# Sensor_Module_0x01_Template_v1.net
KiCad netlist of a schematic drawn in EAGLE
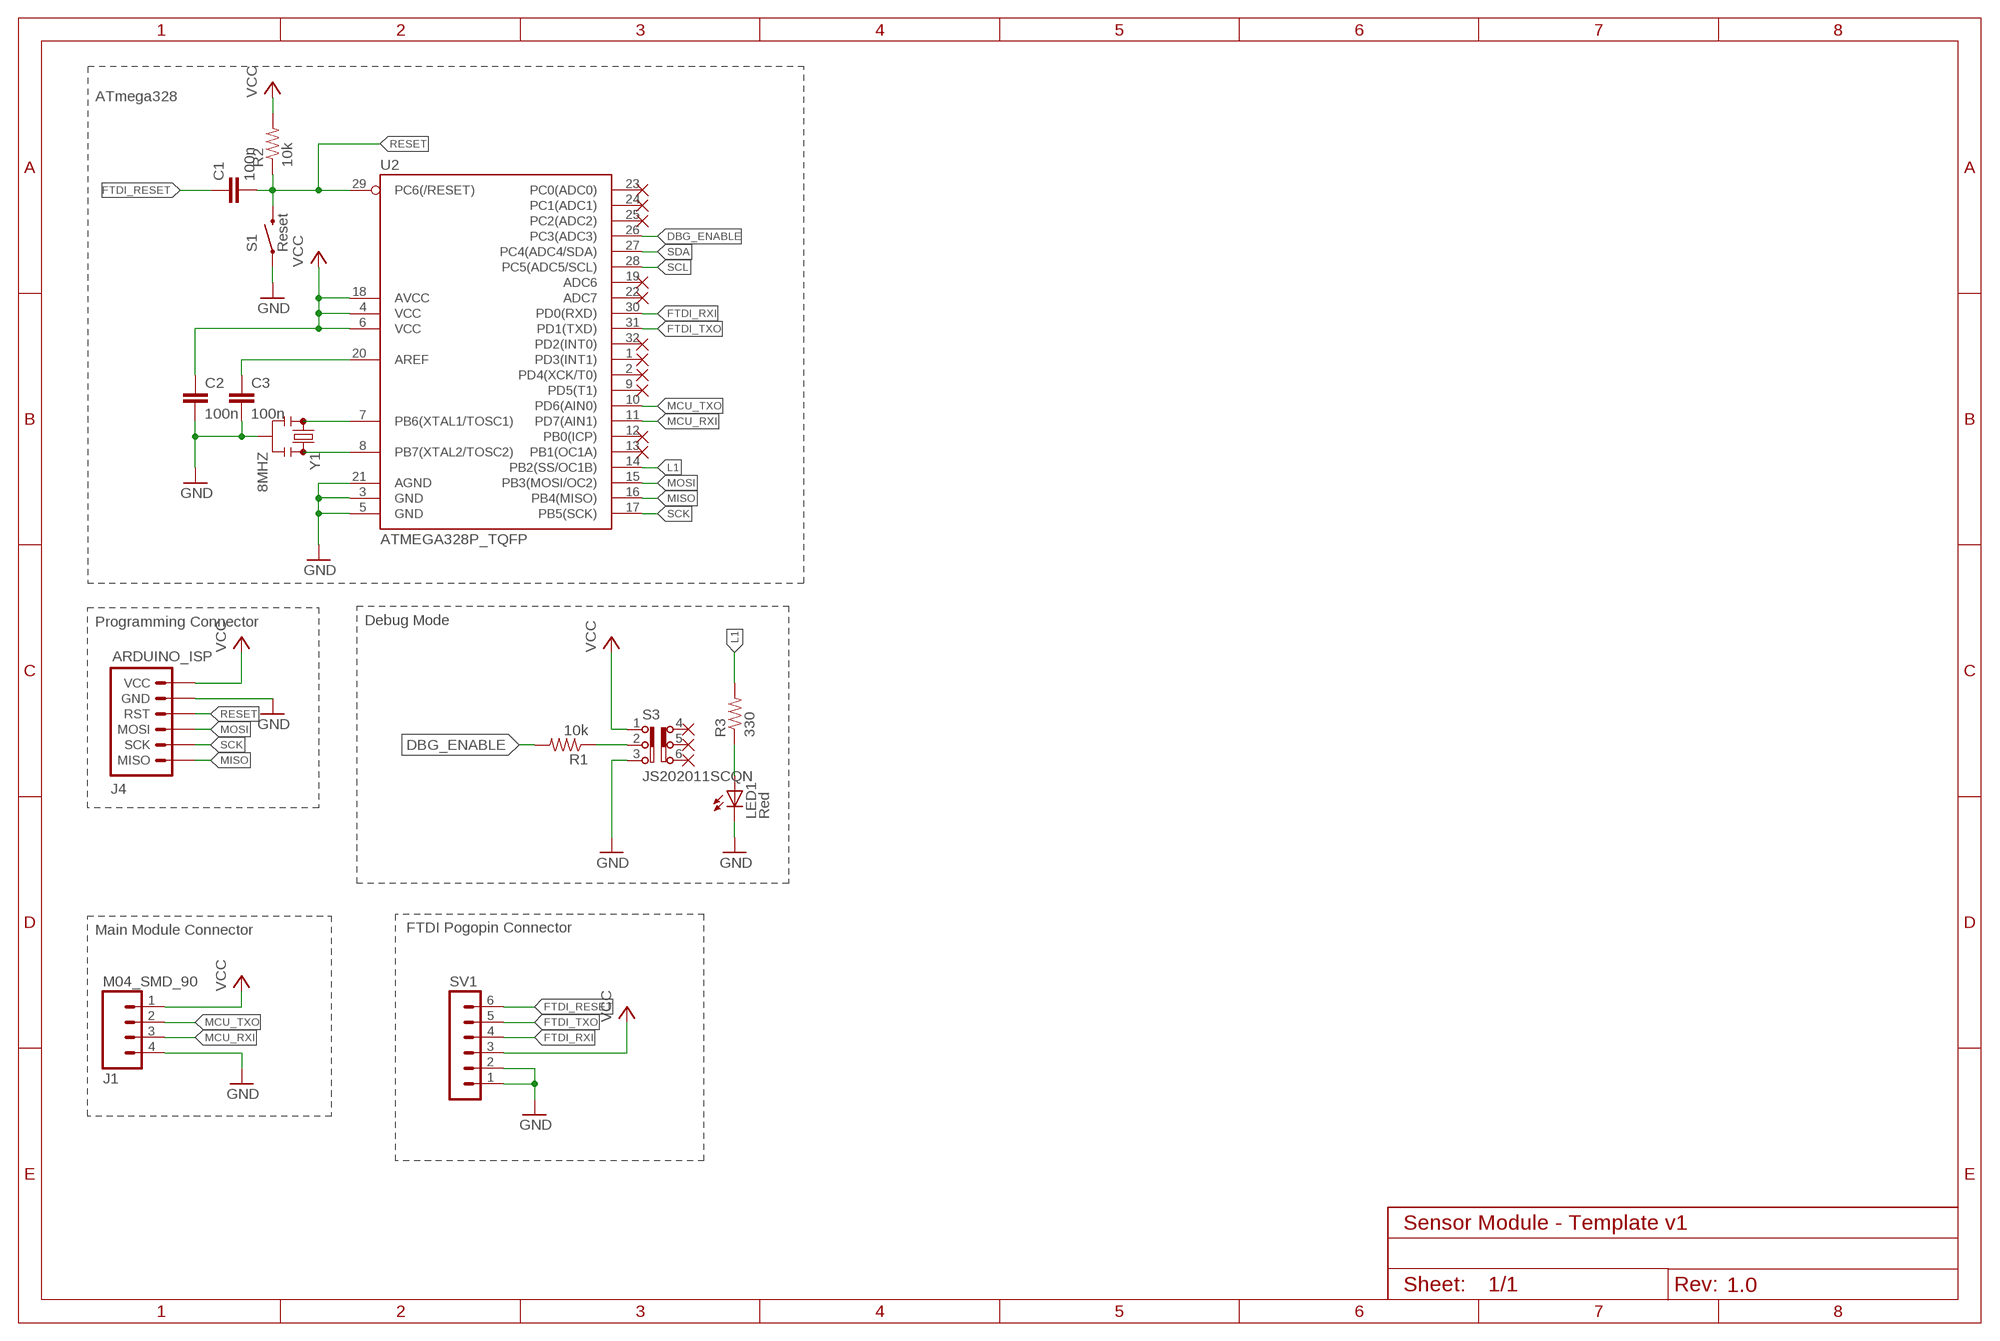
[diagram p0: schematic, sheet 1]

(export (version "E")
  (design (tool "Eeschema 10.0.6"))
  (components
    (comp (ref "C1")
      (value "100n")
      (footprint "eagle-import:C0805")
      (libsource (lib "eagle-import") (part "C"))
    )
    (comp (ref "C2")
      (value "100n")
      (footprint "eagle-import:C0805")
      (libsource (lib "eagle-import") (part "C"))
    )
    (comp (ref "C3")
      (value "100n")
      (footprint "eagle-import:C0805")
      (libsource (lib "eagle-import") (part "C"))
    )
    (comp (ref "J1")
      (value "M04_SMD_90")
      (footprint "eagle-import:M04_SMD_90")
      (libsource (lib "eagle-import") (part "M04_SMD_90"))
    )
    (comp (ref "J4")
      (value "ARDUINO_ISP")
      (footprint "eagle-import:M-2X3")
      (libsource (lib "eagle-import") (part "ARDUINO_ISP"))
    )
    (comp (ref "LED1")
      (value "Red")
      (footprint "eagle-import:SML0805")
      (libsource (lib "eagle-import") (part "LEDSML0805"))
    )
    (comp (ref "R1")
      (value "10k")
      (footprint "eagle-import:0805")
      (libsource (lib "eagle-import") (part "RESISTOR0805-RES"))
    )
    (comp (ref "R2")
      (value "10k")
      (footprint "eagle-import:0805")
      (libsource (lib "eagle-import") (part "RESISTOR0805-RES"))
    )
    (comp (ref "R3")
      (value "330")
      (footprint "eagle-import:0805")
      (libsource (lib "eagle-import") (part "RESISTOR0805-RES"))
    )
    (comp (ref "S1")
      (value "Reset")
      (footprint "eagle-import:M-PUSHBUTTON-SMD")
      (libsource (lib "eagle-import") (part "PUSHBUTTON"))
    )
    (comp (ref "S3")
      (value "JS202011SCQN")
      (footprint "eagle-import:JS202011SCQN")
      (libsource (lib "eagle-import") (part "JS202011SCQN"))
    )
    (comp (ref "SV1")
      (value "MA06-1")
      (footprint "eagle-import:MA06-1")
      (libsource (lib "eagle-import") (part "MA06-1"))
    )
    (comp (ref "U2")
      (value "ATMEGA328P_TQFP")
      (footprint "eagle-import:TQFP32-08")
      (libsource (lib "eagle-import") (part "ATMEGA328P_TQFP"))
    )
    (comp (ref "Y1")
      (value "8MHZ")
      (footprint "eagle-import:RESONATOR-SMD")
      (libsource (lib "eagle-import") (part "RESONATOR8MHZ"))
    )
  )
  (nets
    (net (code "1") (name "DBG_ENABLE") (class "Default")
      (node (ref "R1") (pin "2") (pinfunction "2_2") (pintype "passive"))
      (node (ref "U2") (pin "26") (pinfunction "PC3(ADC3)_26") (pintype "bidirectional"))
    )
    (net (code "2") (name "FTDI_RESET") (class "Default")
      (node (ref "C1") (pin "1") (pinfunction "1_1") (pintype "passive"))
      (node (ref "SV1") (pin "6") (pinfunction "6_6") (pintype "passive"))
    )
    (net (code "3") (name "FTDI_RXI") (class "Default")
      (node (ref "SV1") (pin "4") (pinfunction "4_4") (pintype "passive"))
      (node (ref "U2") (pin "30") (pinfunction "PD0(RXD)_30") (pintype "bidirectional"))
    )
    (net (code "4") (name "FTDI_TXO") (class "Default")
      (node (ref "SV1") (pin "5") (pinfunction "5_5") (pintype "passive"))
      (node (ref "U2") (pin "31") (pinfunction "PD1(TXD)_31") (pintype "bidirectional"))
    )
    (net (code "5") (name "GND") (class "Default")
      (node (ref "C2") (pin "2") (pinfunction "2_2") (pintype "passive"))
      (node (ref "C3") (pin "2") (pinfunction "2_2") (pintype "passive"))
      (node (ref "J1") (pin "4") (pinfunction "4_4") (pintype "passive"))
      (node (ref "J4") (pin "P$5") (pinfunction "GND_P$5") (pintype "passive"))
      (node (ref "LED1") (pin "C") (pinfunction "C_C") (pintype "passive"))
      (node (ref "S1") (pin "1") (pinfunction "LEFT_1") (pintype "passive"))
      (node (ref "S1") (pin "2") (pinfunction "LEFT_2") (pintype "passive"))
      (node (ref "S3") (pin "3") (pinfunction "3_3") (pintype "passive"))
      (node (ref "SV1") (pin "1") (pinfunction "1_1") (pintype "passive"))
      (node (ref "SV1") (pin "2") (pinfunction "2_2") (pintype "passive"))
      (node (ref "U2") (pin "21") (pinfunction "AGND_21") (pintype "bidirectional"))
      (node (ref "U2") (pin "3") (pinfunction "GND_3") (pintype "bidirectional"))
      (node (ref "U2") (pin "5") (pinfunction "GND_5") (pintype "bidirectional"))
      (node (ref "Y1") (pin "2") (pinfunction "2_2") (pintype "passive"))
    )
    (net (code "6") (name "L1") (class "Default")
      (node (ref "R3") (pin "2") (pinfunction "2_2") (pintype "passive"))
      (node (ref "U2") (pin "14") (pinfunction "PB2(SS/OC1B)_14") (pintype "bidirectional"))
    )
    (net (code "7") (name "MCU_RXI") (class "Default")
      (node (ref "J1") (pin "3") (pinfunction "3_3") (pintype "passive"))
      (node (ref "U2") (pin "11") (pinfunction "PD7(AIN1)_11") (pintype "bidirectional"))
    )
    (net (code "8") (name "MCU_TXO") (class "Default")
      (node (ref "J1") (pin "2") (pinfunction "2_2") (pintype "passive"))
      (node (ref "U2") (pin "10") (pinfunction "PD6(AIN0)_10") (pintype "bidirectional"))
    )
    (net (code "9") (name "MISO") (class "Default")
      (node (ref "J4") (pin "P$1") (pinfunction "MISO_P$1") (pintype "passive"))
      (node (ref "U2") (pin "16") (pinfunction "PB4(MISO)_16") (pintype "bidirectional"))
    )
    (net (code "10") (name "MOSI") (class "Default")
      (node (ref "J4") (pin "P$3") (pinfunction "MOSI_P$3") (pintype "passive"))
      (node (ref "U2") (pin "15") (pinfunction "PB3(MOSI/OC2)_15") (pintype "bidirectional"))
    )
    (net (code "11") (name "Net-(LED1-PadA)") (class "Default")
      (node (ref "LED1") (pin "A") (pinfunction "A_A") (pintype "passive"))
      (node (ref "R3") (pin "1") (pinfunction "1_1") (pintype "passive"))
    )
    (net (code "12") (name "Net-(R1-Pad1)") (class "Default")
      (node (ref "R1") (pin "1") (pinfunction "1_1") (pintype "passive"))
      (node (ref "S3") (pin "2") (pinfunction "2_2") (pintype "passive"))
    )
    (net (code "13") (name "Net-(U2-AREF)") (class "Default")
      (node (ref "C3") (pin "1") (pinfunction "1_1") (pintype "passive"))
      (node (ref "U2") (pin "20") (pinfunction "AREF_20") (pintype "bidirectional"))
    )
    (net (code "14") (name "Net-(U2-PB6(XTAL1{slash}TOSC1))") (class "Default")
      (node (ref "U2") (pin "7") (pinfunction "PB6(XTAL1/TOSC1)_7") (pintype "bidirectional"))
      (node (ref "Y1") (pin "1") (pinfunction "1_1") (pintype "passive"))
    )
    (net (code "15") (name "Net-(U2-PB7(XTAL2{slash}TOSC2))") (class "Default")
      (node (ref "U2") (pin "8") (pinfunction "PB7(XTAL2/TOSC2)_8") (pintype "bidirectional"))
      (node (ref "Y1") (pin "3") (pinfunction "3_3") (pintype "passive"))
    )
    (net (code "16") (name "RESET") (class "Default")
      (node (ref "C1") (pin "2") (pinfunction "2_2") (pintype "passive"))
      (node (ref "J4") (pin "P$4") (pinfunction "RST_P$4") (pintype "passive"))
      (node (ref "R2") (pin "1") (pinfunction "1_1") (pintype "passive"))
      (node (ref "S1") (pin "3") (pinfunction "RIGHT_3") (pintype "passive"))
      (node (ref "S1") (pin "4") (pinfunction "RIGHT_4") (pintype "passive"))
      (node (ref "U2") (pin "29") (pinfunction "PC6(/RESET)_29") (pintype "bidirectional"))
    )
    (net (code "17") (name "SCK") (class "Default")
      (node (ref "J4") (pin "P$2") (pinfunction "SCK_P$2") (pintype "passive"))
      (node (ref "U2") (pin "17") (pinfunction "PB5(SCK)_17") (pintype "bidirectional"))
    )
    (net (code "18") (name "SCL") (class "Default")
      (node (ref "U2") (pin "28") (pinfunction "PC5(ADC5/SCL)_28") (pintype "bidirectional"))
    )
    (net (code "19") (name "SDA") (class "Default")
      (node (ref "U2") (pin "27") (pinfunction "PC4(ADC4/SDA)_27") (pintype "bidirectional"))
    )
    (net (code "20") (name "VCC") (class "Default")
      (node (ref "C2") (pin "1") (pinfunction "1_1") (pintype "passive"))
      (node (ref "J1") (pin "1") (pinfunction "1_1") (pintype "passive"))
      (node (ref "J4") (pin "P$6") (pinfunction "VCC_P$6") (pintype "passive"))
      (node (ref "R2") (pin "2") (pinfunction "2_2") (pintype "passive"))
      (node (ref "S3") (pin "1") (pinfunction "1_1") (pintype "passive"))
      (node (ref "SV1") (pin "3") (pinfunction "3_3") (pintype "passive"))
      (node (ref "U2") (pin "18") (pinfunction "AVCC_18") (pintype "bidirectional"))
      (node (ref "U2") (pin "4") (pinfunction "VCC_4") (pintype "bidirectional"))
      (node (ref "U2") (pin "6") (pinfunction "VCC_6") (pintype "bidirectional"))
    )
    (net (code "21") (name "unconnected-(S3-Pad4)") (class "Default")
      (node (ref "S3") (pin "4") (pinfunction "4_4") (pintype "passive"))
    )
    (net (code "22") (name "unconnected-(S3-Pad5)") (class "Default")
      (node (ref "S3") (pin "5") (pinfunction "5_5") (pintype "passive"))
    )
    (net (code "23") (name "unconnected-(S3-Pad6)") (class "Default")
      (node (ref "S3") (pin "6") (pinfunction "6_6") (pintype "passive"))
    )
    (net (code "24") (name "unconnected-(U2-ADC6-Pad19)") (class "Default")
      (node (ref "U2") (pin "19") (pinfunction "ADC6_19") (pintype "bidirectional"))
    )
    (net (code "25") (name "unconnected-(U2-ADC7-Pad22)") (class "Default")
      (node (ref "U2") (pin "22") (pinfunction "ADC7_22") (pintype "bidirectional"))
    )
    (net (code "26") (name "unconnected-(U2-PB0(ICP)-Pad12)") (class "Default")
      (node (ref "U2") (pin "12") (pinfunction "PB0(ICP)_12") (pintype "bidirectional"))
    )
    (net (code "27") (name "unconnected-(U2-PB1(OC1A)-Pad13)") (class "Default")
      (node (ref "U2") (pin "13") (pinfunction "PB1(OC1A)_13") (pintype "bidirectional"))
    )
    (net (code "28") (name "unconnected-(U2-PC0(ADC0)-Pad23)") (class "Default")
      (node (ref "U2") (pin "23") (pinfunction "PC0(ADC0)_23") (pintype "bidirectional"))
    )
    (net (code "29") (name "unconnected-(U2-PC1(ADC1)-Pad24)") (class "Default")
      (node (ref "U2") (pin "24") (pinfunction "PC1(ADC1)_24") (pintype "bidirectional"))
    )
    (net (code "30") (name "unconnected-(U2-PC2(ADC2)-Pad25)") (class "Default")
      (node (ref "U2") (pin "25") (pinfunction "PC2(ADC2)_25") (pintype "bidirectional"))
    )
    (net (code "31") (name "unconnected-(U2-PD2(INT0)-Pad32)") (class "Default")
      (node (ref "U2") (pin "32") (pinfunction "PD2(INT0)_32") (pintype "bidirectional"))
    )
    (net (code "32") (name "unconnected-(U2-PD3(INT1)-Pad1)") (class "Default")
      (node (ref "U2") (pin "1") (pinfunction "PD3(INT1)_1") (pintype "bidirectional"))
    )
    (net (code "33") (name "unconnected-(U2-PD4(XCK{slash}T0)-Pad2)") (class "Default")
      (node (ref "U2") (pin "2") (pinfunction "PD4(XCK/T0)_2") (pintype "bidirectional"))
    )
    (net (code "34") (name "unconnected-(U2-PD5(T1)-Pad9)") (class "Default")
      (node (ref "U2") (pin "9") (pinfunction "PD5(T1)_9") (pintype "bidirectional"))
    )
  )
)
